# PART-02-_R100-149.net
KiCad netlist of a schematic drawn in Altium Designer
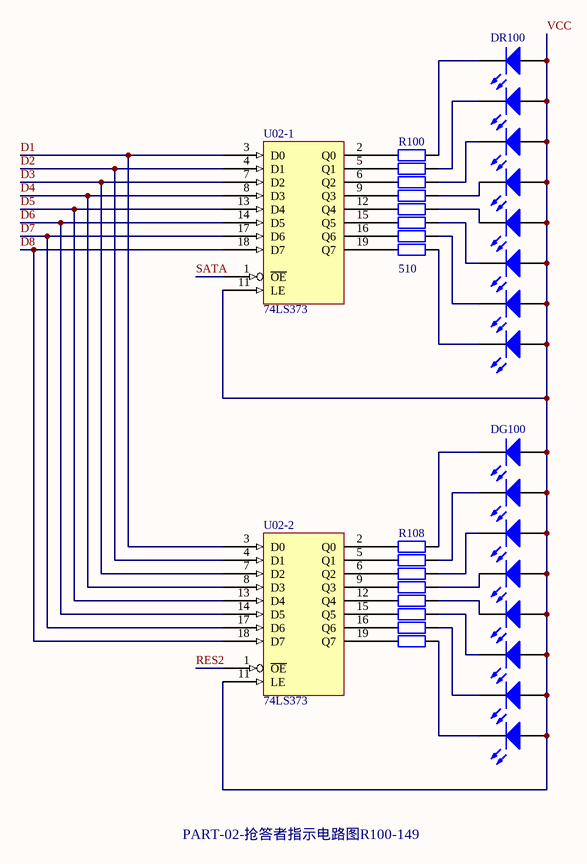
[diagram p0: PART-02-抢答者指示电路图R100-149.SchDoc]

(export (version "E")
  (design (tool "Eeschema 10.0.6"))
  (components
    (comp (ref "DG100")
      (value "LED")
      (footprint "LED-0")
      (description "Typical INFRARED GaAs LED")
      (fields (field (name "PUBLISHER") "Altium Limited"))
      (libsource (lib "Miscellaneous Devices") (part "LED0"))
    )
    (comp (ref "DG101")
      (value "LED")
      (footprint "LED-0")
      (description "Typical INFRARED GaAs LED")
      (fields (field (name "PUBLISHER") "Altium Limited"))
      (libsource (lib "Miscellaneous Devices") (part "LED0"))
    )
    (comp (ref "DG102")
      (value "LED")
      (footprint "LED-0")
      (description "Typical INFRARED GaAs LED")
      (fields (field (name "PUBLISHER") "Altium Limited"))
      (libsource (lib "Miscellaneous Devices") (part "LED0"))
    )
    (comp (ref "DG103")
      (value "LED")
      (footprint "LED-0")
      (description "Typical INFRARED GaAs LED")
      (fields (field (name "PUBLISHER") "Altium Limited"))
      (libsource (lib "Miscellaneous Devices") (part "LED0"))
    )
    (comp (ref "DG104")
      (value "LED")
      (footprint "LED-0")
      (description "Typical INFRARED GaAs LED")
      (fields (field (name "PUBLISHER") "Altium Limited"))
      (libsource (lib "Miscellaneous Devices") (part "LED0"))
    )
    (comp (ref "DG105")
      (value "LED")
      (footprint "LED-0")
      (description "Typical INFRARED GaAs LED")
      (fields (field (name "PUBLISHER") "Altium Limited"))
      (libsource (lib "Miscellaneous Devices") (part "LED0"))
    )
    (comp (ref "DG106")
      (value "LED")
      (footprint "LED-0")
      (description "Typical INFRARED GaAs LED")
      (fields (field (name "PUBLISHER") "Altium Limited"))
      (libsource (lib "Miscellaneous Devices") (part "LED0"))
    )
    (comp (ref "DG107")
      (value "LED")
      (footprint "LED-0")
      (description "Typical INFRARED GaAs LED")
      (fields (field (name "PUBLISHER") "Altium Limited"))
      (libsource (lib "Miscellaneous Devices") (part "LED0"))
    )
    (comp (ref "DR100")
      (value "LED")
      (footprint "LED-0")
      (description "Typical INFRARED GaAs LED")
      (fields (field (name "PUBLISHER") "Altium Limited"))
      (libsource (lib "Miscellaneous Devices") (part "LED0"))
    )
    (comp (ref "DR101")
      (value "LED")
      (footprint "LED-0")
      (description "Typical INFRARED GaAs LED")
      (fields (field (name "PUBLISHER") "Altium Limited"))
      (libsource (lib "Miscellaneous Devices") (part "LED0"))
    )
    (comp (ref "DR102")
      (value "LED")
      (footprint "LED-0")
      (description "Typical INFRARED GaAs LED")
      (fields (field (name "PUBLISHER") "Altium Limited"))
      (libsource (lib "Miscellaneous Devices") (part "LED0"))
    )
    (comp (ref "DR103")
      (value "LED")
      (footprint "LED-0")
      (description "Typical INFRARED GaAs LED")
      (fields (field (name "PUBLISHER") "Altium Limited"))
      (libsource (lib "Miscellaneous Devices") (part "LED0"))
    )
    (comp (ref "DR104")
      (value "LED")
      (footprint "LED-0")
      (description "Typical INFRARED GaAs LED")
      (fields (field (name "PUBLISHER") "Altium Limited"))
      (libsource (lib "Miscellaneous Devices") (part "LED0"))
    )
    (comp (ref "DR105")
      (value "LED")
      (footprint "LED-0")
      (description "Typical INFRARED GaAs LED")
      (fields (field (name "PUBLISHER") "Altium Limited"))
      (libsource (lib "Miscellaneous Devices") (part "LED0"))
    )
    (comp (ref "DR106")
      (value "LED")
      (footprint "LED-0")
      (description "Typical INFRARED GaAs LED")
      (fields (field (name "PUBLISHER") "Altium Limited"))
      (libsource (lib "Miscellaneous Devices") (part "LED0"))
    )
    (comp (ref "DR107")
      (value "LED")
      (footprint "LED-0")
      (description "Typical INFRARED GaAs LED")
      (fields (field (name "PUBLISHER") "Altium Limited"))
      (libsource (lib "Miscellaneous Devices") (part "LED0"))
    )
    (comp (ref "R100")
      (value "510")
      (footprint "AXIAL-0.4")
      (description "Resistor")
      (fields (field (name "Comment") "Res2") (field (name "PUBLISHER") "Altium Limited"))
      (libsource (lib "Miscellaneous Devices") (part "Res2"))
    )
    (comp (ref "R101")
      (value "Res2")
      (footprint "AXIAL-0.4")
      (description "Resistor")
      (fields (field (name "PUBLISHER") "Altium Limited"))
      (libsource (lib "Miscellaneous Devices") (part "Res2"))
    )
    (comp (ref "R102")
      (value "Res2")
      (footprint "AXIAL-0.4")
      (description "Resistor")
      (fields (field (name "PUBLISHER") "Altium Limited"))
      (libsource (lib "Miscellaneous Devices") (part "Res2"))
    )
    (comp (ref "R103")
      (value "Res2")
      (footprint "AXIAL-0.4")
      (description "Resistor")
      (fields (field (name "PUBLISHER") "Altium Limited"))
      (libsource (lib "Miscellaneous Devices") (part "Res2"))
    )
    (comp (ref "R104")
      (value "Res2")
      (footprint "AXIAL-0.4")
      (description "Resistor")
      (fields (field (name "PUBLISHER") "Altium Limited"))
      (libsource (lib "Miscellaneous Devices") (part "Res2"))
    )
    (comp (ref "R105")
      (value "Res2")
      (footprint "AXIAL-0.4")
      (description "Resistor")
      (fields (field (name "PUBLISHER") "Altium Limited"))
      (libsource (lib "Miscellaneous Devices") (part "Res2"))
    )
    (comp (ref "R106")
      (value "Res2")
      (footprint "AXIAL-0.4")
      (description "Resistor")
      (fields (field (name "PUBLISHER") "Altium Limited"))
      (libsource (lib "Miscellaneous Devices") (part "Res2"))
    )
    (comp (ref "R107")
      (value "Res2")
      (footprint "AXIAL-0.4")
      (description "Resistor")
      (fields (field (name "PUBLISHER") "Altium Limited"))
      (libsource (lib "Miscellaneous Devices") (part "Res2"))
    )
    (comp (ref "R108")
      (value "Res2")
      (footprint "AXIAL-0.4")
      (description "Resistor")
      (fields (field (name "PUBLISHER") "Altium Limited"))
      (libsource (lib "Miscellaneous Devices") (part "Res2"))
    )
    (comp (ref "R109")
      (value "Res2")
      (footprint "AXIAL-0.4")
      (description "Resistor")
      (fields (field (name "PUBLISHER") "Altium Limited"))
      (libsource (lib "Miscellaneous Devices") (part "Res2"))
    )
    (comp (ref "R110")
      (value "Res2")
      (footprint "AXIAL-0.4")
      (description "Resistor")
      (fields (field (name "PUBLISHER") "Altium Limited"))
      (libsource (lib "Miscellaneous Devices") (part "Res2"))
    )
    (comp (ref "R111")
      (value "Res2")
      (footprint "AXIAL-0.4")
      (description "Resistor")
      (fields (field (name "PUBLISHER") "Altium Limited"))
      (libsource (lib "Miscellaneous Devices") (part "Res2"))
    )
    (comp (ref "R112")
      (value "Res2")
      (footprint "AXIAL-0.4")
      (description "Resistor")
      (fields (field (name "PUBLISHER") "Altium Limited"))
      (libsource (lib "Miscellaneous Devices") (part "Res2"))
    )
    (comp (ref "R113")
      (value "Res2")
      (footprint "AXIAL-0.4")
      (description "Resistor")
      (fields (field (name "PUBLISHER") "Altium Limited"))
      (libsource (lib "Miscellaneous Devices") (part "Res2"))
    )
    (comp (ref "R114")
      (value "Res2")
      (footprint "AXIAL-0.4")
      (description "Resistor")
      (fields (field (name "PUBLISHER") "Altium Limited"))
      (libsource (lib "Miscellaneous Devices") (part "Res2"))
    )
    (comp (ref "R115")
      (value "Res2")
      (footprint "AXIAL-0.4")
      (description "Resistor")
      (fields (field (name "PUBLISHER") "Altium Limited"))
      (libsource (lib "Miscellaneous Devices") (part "Res2"))
    )
    (comp (ref "U02-1")
      (value "74LS373")
      (footprint "DIP-20")
      (libsource (lib "Protel DOS Schematic TTL") (part "74LS373"))
    )
    (comp (ref "U02-2")
      (value "74LS373")
      (footprint "DIP-20")
      (libsource (lib "Protel DOS Schematic TTL") (part "74LS373"))
    )
  )
  (nets
    (net (code "1") (name "/D1") (class "Default")
      (node (ref "U02-1") (pin "3") (pinfunction "D0_3") (pintype "input"))
      (node (ref "U02-2") (pin "3") (pinfunction "D0_3") (pintype "input"))
    )
    (net (code "2") (name "/D2") (class "Default")
      (node (ref "U02-1") (pin "4") (pinfunction "D1_4") (pintype "input"))
      (node (ref "U02-2") (pin "4") (pinfunction "D1_4") (pintype "input"))
    )
    (net (code "3") (name "/D3") (class "Default")
      (node (ref "U02-1") (pin "7") (pinfunction "D2_7") (pintype "input"))
      (node (ref "U02-2") (pin "7") (pinfunction "D2_7") (pintype "input"))
    )
    (net (code "4") (name "/D4") (class "Default")
      (node (ref "U02-1") (pin "8") (pinfunction "D3_8") (pintype "input"))
      (node (ref "U02-2") (pin "8") (pinfunction "D3_8") (pintype "input"))
    )
    (net (code "5") (name "/D5") (class "Default")
      (node (ref "U02-1") (pin "13") (pinfunction "D4_13") (pintype "input"))
      (node (ref "U02-2") (pin "13") (pinfunction "D4_13") (pintype "input"))
    )
    (net (code "6") (name "/D6") (class "Default")
      (node (ref "U02-1") (pin "14") (pinfunction "D5_14") (pintype "input"))
      (node (ref "U02-2") (pin "14") (pinfunction "D5_14") (pintype "input"))
    )
    (net (code "7") (name "/D7") (class "Default")
      (node (ref "U02-1") (pin "17") (pinfunction "D6_17") (pintype "input"))
      (node (ref "U02-2") (pin "17") (pinfunction "D6_17") (pintype "input"))
    )
    (net (code "8") (name "/D8") (class "Default")
      (node (ref "U02-1") (pin "18") (pinfunction "D7_18") (pintype "input"))
      (node (ref "U02-2") (pin "18") (pinfunction "D7_18") (pintype "input"))
    )
    (net (code "9") (name "/RES2") (class "Default")
      (node (ref "U02-2") (pin "1") (pinfunction "~{OE}_1") (pintype "input"))
    )
    (net (code "10") (name "/SATA") (class "Default")
      (node (ref "U02-1") (pin "1") (pinfunction "~{OE}_1") (pintype "input"))
    )
    (net (code "11") (name "GND") (class "Default")
      (node (ref "U02-1") (pin "10") (pinfunction "GND_10") (pintype "power_in"))
      (node (ref "U02-2") (pin "10") (pinfunction "GND_10") (pintype "power_in"))
    )
    (net (code "12") (name "Net-(DG100-K)") (class "Default")
      (node (ref "DG100") (pin "2") (pinfunction "K_2") (pintype "passive"))
      (node (ref "R108") (pin "2") (pinfunction "2_2") (pintype "passive"))
    )
    (net (code "13") (name "Net-(DG101-K)") (class "Default")
      (node (ref "DG101") (pin "2") (pinfunction "K_2") (pintype "passive"))
      (node (ref "R109") (pin "2") (pinfunction "2_2") (pintype "passive"))
    )
    (net (code "14") (name "Net-(DG102-K)") (class "Default")
      (node (ref "DG102") (pin "2") (pinfunction "K_2") (pintype "passive"))
      (node (ref "R110") (pin "2") (pinfunction "2_2") (pintype "passive"))
    )
    (net (code "15") (name "Net-(DG103-K)") (class "Default")
      (node (ref "DG103") (pin "2") (pinfunction "K_2") (pintype "passive"))
      (node (ref "R111") (pin "2") (pinfunction "2_2") (pintype "passive"))
    )
    (net (code "16") (name "Net-(DG104-K)") (class "Default")
      (node (ref "DG104") (pin "2") (pinfunction "K_2") (pintype "passive"))
      (node (ref "R112") (pin "2") (pinfunction "2_2") (pintype "passive"))
    )
    (net (code "17") (name "Net-(DG105-K)") (class "Default")
      (node (ref "DG105") (pin "2") (pinfunction "K_2") (pintype "passive"))
      (node (ref "R113") (pin "2") (pinfunction "2_2") (pintype "passive"))
    )
    (net (code "18") (name "Net-(DG106-K)") (class "Default")
      (node (ref "DG106") (pin "2") (pinfunction "K_2") (pintype "passive"))
      (node (ref "R114") (pin "2") (pinfunction "2_2") (pintype "passive"))
    )
    (net (code "19") (name "Net-(DG107-K)") (class "Default")
      (node (ref "DG107") (pin "2") (pinfunction "K_2") (pintype "passive"))
      (node (ref "R115") (pin "2") (pinfunction "2_2") (pintype "passive"))
    )
    (net (code "20") (name "Net-(DR100-K)") (class "Default")
      (node (ref "DR100") (pin "2") (pinfunction "K_2") (pintype "passive"))
      (node (ref "R100") (pin "2") (pinfunction "2_2") (pintype "passive"))
    )
    (net (code "21") (name "Net-(DR101-K)") (class "Default")
      (node (ref "DR101") (pin "2") (pinfunction "K_2") (pintype "passive"))
      (node (ref "R101") (pin "2") (pinfunction "2_2") (pintype "passive"))
    )
    (net (code "22") (name "Net-(DR102-K)") (class "Default")
      (node (ref "DR102") (pin "2") (pinfunction "K_2") (pintype "passive"))
      (node (ref "R102") (pin "2") (pinfunction "2_2") (pintype "passive"))
    )
    (net (code "23") (name "Net-(DR103-K)") (class "Default")
      (node (ref "DR103") (pin "2") (pinfunction "K_2") (pintype "passive"))
      (node (ref "R103") (pin "2") (pinfunction "2_2") (pintype "passive"))
    )
    (net (code "24") (name "Net-(DR104-K)") (class "Default")
      (node (ref "DR104") (pin "2") (pinfunction "K_2") (pintype "passive"))
      (node (ref "R104") (pin "2") (pinfunction "2_2") (pintype "passive"))
    )
    (net (code "25") (name "Net-(DR105-K)") (class "Default")
      (node (ref "DR105") (pin "2") (pinfunction "K_2") (pintype "passive"))
      (node (ref "R105") (pin "2") (pinfunction "2_2") (pintype "passive"))
    )
    (net (code "26") (name "Net-(DR106-K)") (class "Default")
      (node (ref "DR106") (pin "2") (pinfunction "K_2") (pintype "passive"))
      (node (ref "R106") (pin "2") (pinfunction "2_2") (pintype "passive"))
    )
    (net (code "27") (name "Net-(DR107-K)") (class "Default")
      (node (ref "DR107") (pin "2") (pinfunction "K_2") (pintype "passive"))
      (node (ref "R107") (pin "2") (pinfunction "2_2") (pintype "passive"))
    )
    (net (code "28") (name "Net-(U02-1-Q0)") (class "Default")
      (node (ref "R100") (pin "1") (pinfunction "1_1") (pintype "passive"))
      (node (ref "U02-1") (pin "2") (pinfunction "Q0_2") (pintype "tri_state"))
    )
    (net (code "29") (name "Net-(U02-1-Q1)") (class "Default")
      (node (ref "R101") (pin "1") (pinfunction "1_1") (pintype "passive"))
      (node (ref "U02-1") (pin "5") (pinfunction "Q1_5") (pintype "tri_state"))
    )
    (net (code "30") (name "Net-(U02-1-Q2)") (class "Default")
      (node (ref "R102") (pin "1") (pinfunction "1_1") (pintype "passive"))
      (node (ref "U02-1") (pin "6") (pinfunction "Q2_6") (pintype "tri_state"))
    )
    (net (code "31") (name "Net-(U02-1-Q3)") (class "Default")
      (node (ref "R103") (pin "1") (pinfunction "1_1") (pintype "passive"))
      (node (ref "U02-1") (pin "9") (pinfunction "Q3_9") (pintype "tri_state"))
    )
    (net (code "32") (name "Net-(U02-1-Q4)") (class "Default")
      (node (ref "R104") (pin "1") (pinfunction "1_1") (pintype "passive"))
      (node (ref "U02-1") (pin "12") (pinfunction "Q4_12") (pintype "tri_state"))
    )
    (net (code "33") (name "Net-(U02-1-Q5)") (class "Default")
      (node (ref "R105") (pin "1") (pinfunction "1_1") (pintype "passive"))
      (node (ref "U02-1") (pin "15") (pinfunction "Q5_15") (pintype "tri_state"))
    )
    (net (code "34") (name "Net-(U02-1-Q6)") (class "Default")
      (node (ref "R106") (pin "1") (pinfunction "1_1") (pintype "passive"))
      (node (ref "U02-1") (pin "16") (pinfunction "Q6_16") (pintype "tri_state"))
    )
    (net (code "35") (name "Net-(U02-1-Q7)") (class "Default")
      (node (ref "R107") (pin "1") (pinfunction "1_1") (pintype "passive"))
      (node (ref "U02-1") (pin "19") (pinfunction "Q7_19") (pintype "tri_state"))
    )
    (net (code "36") (name "Net-(U02-2-Q0)") (class "Default")
      (node (ref "R108") (pin "1") (pinfunction "1_1") (pintype "passive"))
      (node (ref "U02-2") (pin "2") (pinfunction "Q0_2") (pintype "tri_state"))
    )
    (net (code "37") (name "Net-(U02-2-Q1)") (class "Default")
      (node (ref "R109") (pin "1") (pinfunction "1_1") (pintype "passive"))
      (node (ref "U02-2") (pin "5") (pinfunction "Q1_5") (pintype "tri_state"))
    )
    (net (code "38") (name "Net-(U02-2-Q2)") (class "Default")
      (node (ref "R110") (pin "1") (pinfunction "1_1") (pintype "passive"))
      (node (ref "U02-2") (pin "6") (pinfunction "Q2_6") (pintype "tri_state"))
    )
    (net (code "39") (name "Net-(U02-2-Q3)") (class "Default")
      (node (ref "R111") (pin "1") (pinfunction "1_1") (pintype "passive"))
      (node (ref "U02-2") (pin "9") (pinfunction "Q3_9") (pintype "tri_state"))
    )
    (net (code "40") (name "Net-(U02-2-Q4)") (class "Default")
      (node (ref "R112") (pin "1") (pinfunction "1_1") (pintype "passive"))
      (node (ref "U02-2") (pin "12") (pinfunction "Q4_12") (pintype "tri_state"))
    )
    (net (code "41") (name "Net-(U02-2-Q5)") (class "Default")
      (node (ref "R113") (pin "1") (pinfunction "1_1") (pintype "passive"))
      (node (ref "U02-2") (pin "15") (pinfunction "Q5_15") (pintype "tri_state"))
    )
    (net (code "42") (name "Net-(U02-2-Q6)") (class "Default")
      (node (ref "R114") (pin "1") (pinfunction "1_1") (pintype "passive"))
      (node (ref "U02-2") (pin "16") (pinfunction "Q6_16") (pintype "tri_state"))
    )
    (net (code "43") (name "Net-(U02-2-Q7)") (class "Default")
      (node (ref "R115") (pin "1") (pinfunction "1_1") (pintype "passive"))
      (node (ref "U02-2") (pin "19") (pinfunction "Q7_19") (pintype "tri_state"))
    )
    (net (code "44") (name "VCC") (class "Default")
      (node (ref "DG100") (pin "1") (pinfunction "A_1") (pintype "passive"))
      (node (ref "DG101") (pin "1") (pinfunction "A_1") (pintype "passive"))
      (node (ref "DG102") (pin "1") (pinfunction "A_1") (pintype "passive"))
      (node (ref "DG103") (pin "1") (pinfunction "A_1") (pintype "passive"))
      (node (ref "DG104") (pin "1") (pinfunction "A_1") (pintype "passive"))
      (node (ref "DG105") (pin "1") (pinfunction "A_1") (pintype "passive"))
      (node (ref "DG106") (pin "1") (pinfunction "A_1") (pintype "passive"))
      (node (ref "DG107") (pin "1") (pinfunction "A_1") (pintype "passive"))
      (node (ref "DR100") (pin "1") (pinfunction "A_1") (pintype "passive"))
      (node (ref "DR101") (pin "1") (pinfunction "A_1") (pintype "passive"))
      (node (ref "DR102") (pin "1") (pinfunction "A_1") (pintype "passive"))
      (node (ref "DR103") (pin "1") (pinfunction "A_1") (pintype "passive"))
      (node (ref "DR104") (pin "1") (pinfunction "A_1") (pintype "passive"))
      (node (ref "DR105") (pin "1") (pinfunction "A_1") (pintype "passive"))
      (node (ref "DR106") (pin "1") (pinfunction "A_1") (pintype "passive"))
      (node (ref "DR107") (pin "1") (pinfunction "A_1") (pintype "passive"))
      (node (ref "U02-1") (pin "11") (pinfunction "LE_11") (pintype "input"))
      (node (ref "U02-1") (pin "20") (pinfunction "VCC_20") (pintype "power_in"))
      (node (ref "U02-2") (pin "11") (pinfunction "LE_11") (pintype "input"))
      (node (ref "U02-2") (pin "20") (pinfunction "VCC_20") (pintype "power_in"))
    )
  )
)
